# c64saver.net
KiCad netlist of a schematic drawn in EAGLE
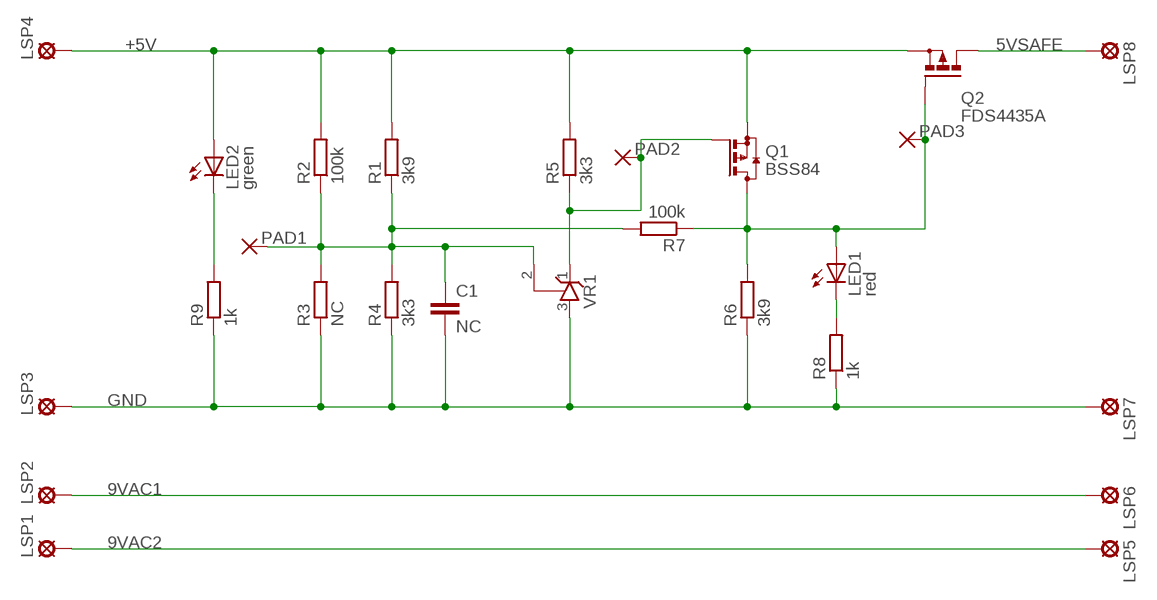
[diagram p0: schematic, sheet 1]

(export (version "E")
  (design (tool "Eeschema 10.0.6"))
  (components
    (comp (ref "C1")
      (value "NC")
      (footprint "eagle-import:C0603")
      (libsource (lib "eagle-import") (part "C-EUC0603"))
    )
    (comp (ref "LED1")
      (value "red")
      (footprint "eagle-import:CHIPLED_1206")
      (libsource (lib "eagle-import") (part "LEDCHIPLED_1206"))
    )
    (comp (ref "LED2")
      (value "green")
      (footprint "eagle-import:CHIPLED_1206")
      (libsource (lib "eagle-import") (part "LEDCHIPLED_1206"))
    )
    (comp (ref "LSP1")
      (value "SE14")
      (footprint "eagle-import:SE14")
      (libsource (lib "eagle-import") (part "SE14"))
    )
    (comp (ref "LSP2")
      (value "SE14")
      (footprint "eagle-import:SE14")
      (libsource (lib "eagle-import") (part "SE14"))
    )
    (comp (ref "LSP3")
      (value "SE14")
      (footprint "eagle-import:SE14")
      (libsource (lib "eagle-import") (part "SE14"))
    )
    (comp (ref "LSP4")
      (value "SE14")
      (footprint "eagle-import:SE14")
      (libsource (lib "eagle-import") (part "SE14"))
    )
    (comp (ref "LSP5")
      (value "SE14")
      (footprint "eagle-import:SE14")
      (libsource (lib "eagle-import") (part "SE14"))
    )
    (comp (ref "LSP6")
      (value "SE14")
      (footprint "eagle-import:SE14")
      (libsource (lib "eagle-import") (part "SE14"))
    )
    (comp (ref "LSP7")
      (value "SE14")
      (footprint "eagle-import:SE14")
      (libsource (lib "eagle-import") (part "SE14"))
    )
    (comp (ref "LSP8")
      (value "SE14")
      (footprint "eagle-import:SE14")
      (libsource (lib "eagle-import") (part "SE14"))
    )
    (comp (ref "PAD1")
      (value "SMD2")
      (footprint "eagle-import:SMD1,27-2,54")
      (libsource (lib "eagle-import") (part "SMD2"))
    )
    (comp (ref "PAD2")
      (value "SMD2")
      (footprint "eagle-import:SMD1,27-2,54")
      (libsource (lib "eagle-import") (part "SMD2"))
    )
    (comp (ref "PAD3")
      (value "SMD2")
      (footprint "eagle-import:SMD1,27-2,54")
      (libsource (lib "eagle-import") (part "SMD2"))
    )
    (comp (ref "Q1")
      (value "BSS84")
      (footprint "eagle-import:SOT23")
      (libsource (lib "eagle-import") (part "BSS84"))
    )
    (comp (ref "Q2")
      (value "FDS4435A")
      (footprint "eagle-import:SO-08")
      (libsource (lib "eagle-import") (part "P-MOSFET-SO8"))
    )
    (comp (ref "R1")
      (value "3k9")
      (footprint "eagle-import:R0603")
      (libsource (lib "eagle-import") (part "R-EU_R0603"))
    )
    (comp (ref "R2")
      (value "100k")
      (footprint "eagle-import:R0603")
      (libsource (lib "eagle-import") (part "R-EU_R0603"))
    )
    (comp (ref "R3")
      (value "NC")
      (footprint "eagle-import:R0603")
      (libsource (lib "eagle-import") (part "R-EU_R0603"))
    )
    (comp (ref "R4")
      (value "3k3")
      (footprint "eagle-import:R0603")
      (libsource (lib "eagle-import") (part "R-EU_R0603"))
    )
    (comp (ref "R5")
      (value "3k3")
      (footprint "eagle-import:R0603")
      (libsource (lib "eagle-import") (part "R-EU_R0603"))
    )
    (comp (ref "R6")
      (value "3k9")
      (footprint "eagle-import:R0603")
      (libsource (lib "eagle-import") (part "R-EU_R0603"))
    )
    (comp (ref "R7")
      (value "100k")
      (footprint "eagle-import:R0603")
      (libsource (lib "eagle-import") (part "R-EU_R0603"))
    )
    (comp (ref "R8")
      (value "1k")
      (footprint "eagle-import:R0603")
      (libsource (lib "eagle-import") (part "R-EU_R0603"))
    )
    (comp (ref "R9")
      (value "1k")
      (footprint "eagle-import:R0603")
      (libsource (lib "eagle-import") (part "R-EU_R0603"))
    )
    (comp (ref "VR1")
      (value "TL431CLPSOT23")
      (footprint "eagle-import:SOT23")
      (libsource (lib "eagle-import") (part "TL431CLPSOT23"))
    )
  )
  (nets
    (net (code "1") (name "/+5V") (class "Default")
      (node (ref "LED2") (pin "A") (pinfunction "A_A") (pintype "passive"))
      (node (ref "LSP4") (pin "MP") (pinfunction "MP_MP") (pintype "passive"))
      (node (ref "Q1") (pin "2") (pinfunction "S_2") (pintype "passive"))
      (node (ref "Q2") (pin "1") (pinfunction "S_1") (pintype "passive"))
      (node (ref "Q2") (pin "2") (pinfunction "S_2") (pintype "passive"))
      (node (ref "Q2") (pin "3") (pinfunction "S_3") (pintype "passive"))
      (node (ref "R1") (pin "2") (pinfunction "2_2") (pintype "passive"))
      (node (ref "R2") (pin "2") (pinfunction "2_2") (pintype "passive"))
      (node (ref "R5") (pin "2") (pinfunction "2_2") (pintype "passive"))
    )
    (net (code "2") (name "/5VSAFE") (class "Default")
      (node (ref "LSP8") (pin "MP") (pinfunction "MP_MP") (pintype "passive"))
      (node (ref "Q2") (pin "5") (pinfunction "D_5") (pintype "passive"))
      (node (ref "Q2") (pin "6") (pinfunction "D_6") (pintype "passive"))
      (node (ref "Q2") (pin "7") (pinfunction "D_7") (pintype "passive"))
      (node (ref "Q2") (pin "8") (pinfunction "D_8") (pintype "passive"))
    )
    (net (code "3") (name "/9VAC1") (class "Default")
      (node (ref "LSP2") (pin "MP") (pinfunction "MP_MP") (pintype "passive"))
      (node (ref "LSP6") (pin "MP") (pinfunction "MP_MP") (pintype "passive"))
    )
    (net (code "4") (name "/9VAC2") (class "Default")
      (node (ref "LSP1") (pin "MP") (pinfunction "MP_MP") (pintype "passive"))
      (node (ref "LSP5") (pin "MP") (pinfunction "MP_MP") (pintype "passive"))
    )
    (net (code "5") (name "/GND") (class "Default")
      (node (ref "C1") (pin "2") (pinfunction "2_2") (pintype "passive"))
      (node (ref "LSP3") (pin "MP") (pinfunction "MP_MP") (pintype "passive"))
      (node (ref "LSP7") (pin "MP") (pinfunction "MP_MP") (pintype "passive"))
      (node (ref "R3") (pin "1") (pinfunction "1_1") (pintype "passive"))
      (node (ref "R4") (pin "1") (pinfunction "1_1") (pintype "passive"))
      (node (ref "R6") (pin "1") (pinfunction "1_1") (pintype "passive"))
      (node (ref "R8") (pin "1") (pinfunction "1_1") (pintype "passive"))
      (node (ref "R9") (pin "1") (pinfunction "1_1") (pintype "passive"))
      (node (ref "VR1") (pin "3") (pinfunction "A_3") (pintype "passive"))
    )
    (net (code "6") (name "Net-(LED1-PadC)") (class "Default")
      (node (ref "LED1") (pin "C") (pinfunction "C_C") (pintype "passive"))
      (node (ref "R8") (pin "2") (pinfunction "2_2") (pintype "passive"))
    )
    (net (code "7") (name "Net-(LED2-PadC)") (class "Default")
      (node (ref "LED2") (pin "C") (pinfunction "C_C") (pintype "passive"))
      (node (ref "R9") (pin "2") (pinfunction "2_2") (pintype "passive"))
    )
    (net (code "8") (name "Net-(PAD1-P)") (class "Default")
      (node (ref "C1") (pin "1") (pinfunction "1_1") (pintype "passive"))
      (node (ref "PAD1") (pin "1") (pinfunction "P_1") (pintype "passive"))
      (node (ref "R1") (pin "1") (pinfunction "1_1") (pintype "passive"))
      (node (ref "R2") (pin "1") (pinfunction "1_1") (pintype "passive"))
      (node (ref "R3") (pin "2") (pinfunction "2_2") (pintype "passive"))
      (node (ref "R4") (pin "2") (pinfunction "2_2") (pintype "passive"))
      (node (ref "R7") (pin "2") (pinfunction "2_2") (pintype "passive"))
      (node (ref "VR1") (pin "2") (pinfunction "R_2") (pintype "passive"))
    )
    (net (code "9") (name "Net-(PAD2-P)") (class "Default")
      (node (ref "PAD2") (pin "1") (pinfunction "P_1") (pintype "passive"))
      (node (ref "Q1") (pin "1") (pinfunction "G_1") (pintype "passive"))
      (node (ref "R5") (pin "1") (pinfunction "1_1") (pintype "passive"))
      (node (ref "VR1") (pin "1") (pinfunction "C_1") (pintype "passive"))
    )
    (net (code "10") (name "Net-(PAD3-P)") (class "Default")
      (node (ref "LED1") (pin "A") (pinfunction "A_A") (pintype "passive"))
      (node (ref "PAD3") (pin "1") (pinfunction "P_1") (pintype "passive"))
      (node (ref "Q1") (pin "3") (pinfunction "D_3") (pintype "passive"))
      (node (ref "Q2") (pin "4") (pinfunction "G_4") (pintype "passive"))
      (node (ref "R6") (pin "2") (pinfunction "2_2") (pintype "passive"))
      (node (ref "R7") (pin "1") (pinfunction "1_1") (pintype "passive"))
    )
  )
)
